# PMIC.net
KiCad netlist of a schematic drawn in Altium Designer
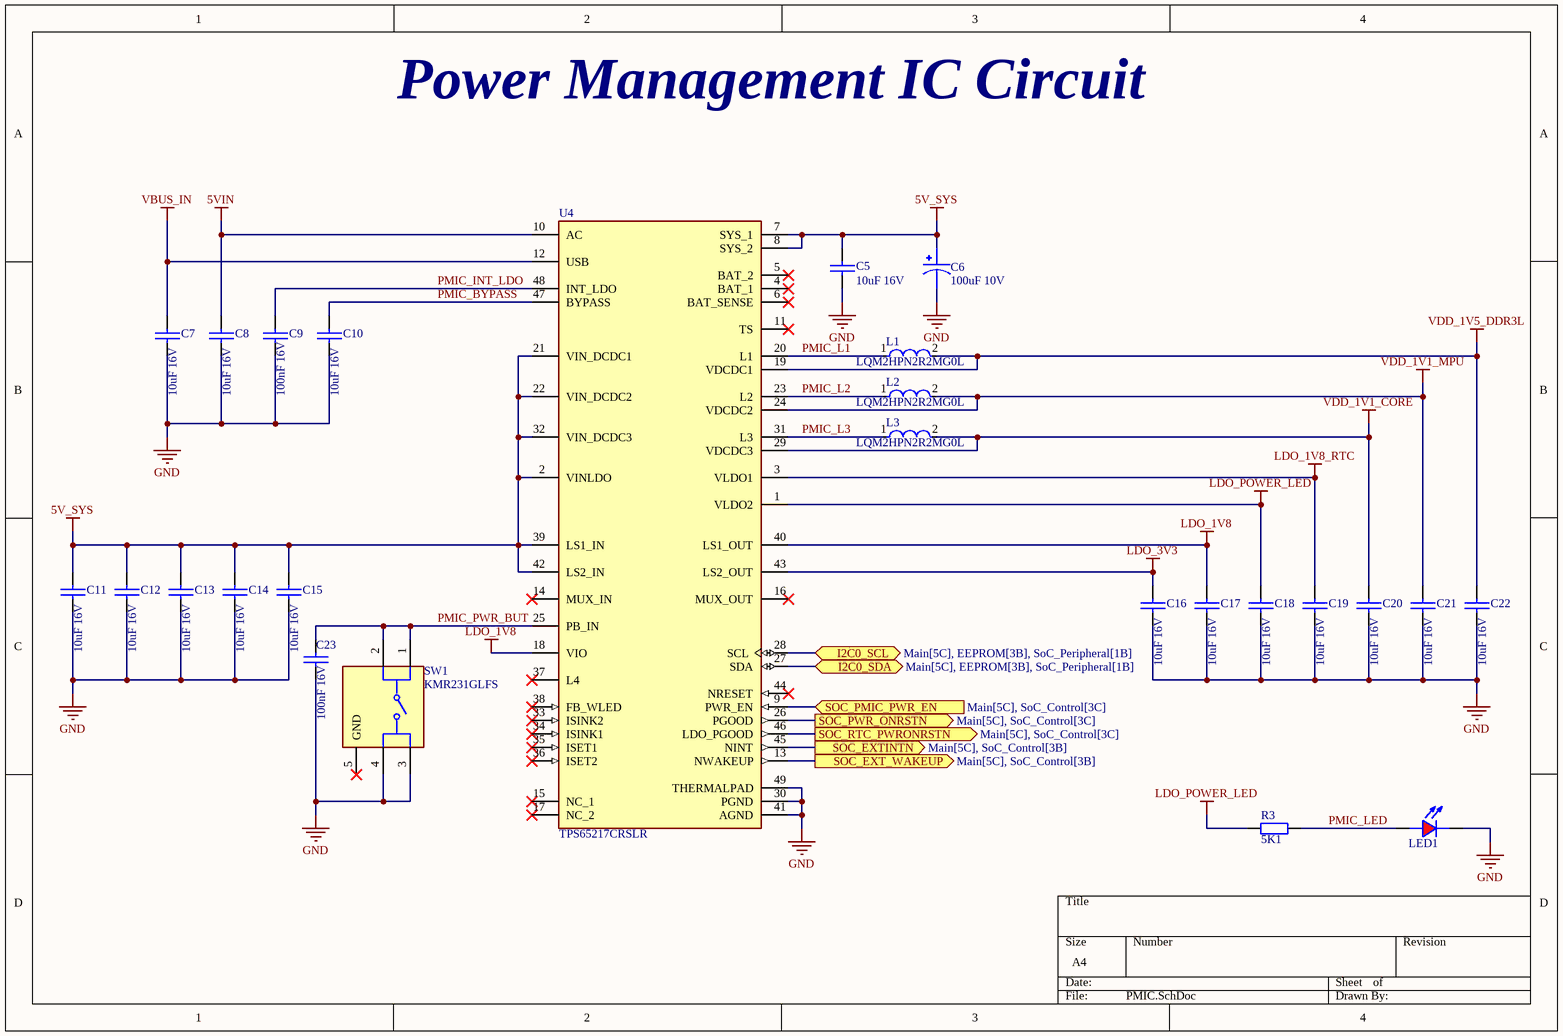
[diagram p0: PMIC.SchDoc]

(export (version "E")
  (design (tool "Eeschema 10.0.6"))
  (components
    (comp (ref "C5")
      (value "10uF 16V")
      (footprint "C_0603")
      (description "Capacitor 0603 SMD")
      (libsource (lib "tor1kkLib") (part "C_0603"))
    )
    (comp (ref "C6")
      (value "100uF 10V")
      (footprint "C_CASE-B")
      (description "Tantalum capacitor CASE-B-3528-21")
      (libsource (lib "tor1kkLib") (part "C_CASE-B-3528-21"))
    )
    (comp (ref "C7")
      (value "10uF 16V")
      (footprint "C_0603")
      (description "Capacitor 0603 SMD")
      (libsource (lib "tor1kkLib") (part "C_0603"))
    )
    (comp (ref "C8")
      (value "10uF 16V")
      (footprint "C_0603")
      (description "Capacitor 0603 SMD")
      (libsource (lib "tor1kkLib") (part "C_0603"))
    )
    (comp (ref "C9")
      (value "100nF 16V")
      (footprint "C_0402")
      (description "Capacitor 0402 SMD")
      (libsource (lib "tor1kkLib") (part "C_0402"))
    )
    (comp (ref "C10")
      (value "10uF 16V")
      (footprint "C_0603")
      (description "Capacitor 0603 SMD")
      (libsource (lib "tor1kkLib") (part "C_0603"))
    )
    (comp (ref "C11")
      (value "10uF 16V")
      (footprint "C_0603")
      (description "Capacitor 0603 SMD")
      (libsource (lib "tor1kkLib") (part "C_0603"))
    )
    (comp (ref "C12")
      (value "10uF 16V")
      (footprint "C_0603")
      (description "Capacitor 0603 SMD")
      (libsource (lib "tor1kkLib") (part "C_0603"))
    )
    (comp (ref "C13")
      (value "10uF 16V")
      (footprint "C_0603")
      (description "Capacitor 0603 SMD")
      (libsource (lib "tor1kkLib") (part "C_0603"))
    )
    (comp (ref "C14")
      (value "10uF 16V")
      (footprint "C_0603")
      (description "Capacitor 0603 SMD")
      (libsource (lib "tor1kkLib") (part "C_0603"))
    )
    (comp (ref "C15")
      (value "10uF 16V")
      (footprint "C_0603")
      (description "Capacitor 0603 SMD")
      (libsource (lib "tor1kkLib") (part "C_0603"))
    )
    (comp (ref "C16")
      (value "10uF 16V")
      (footprint "C_0603")
      (description "Capacitor 0603 SMD")
      (libsource (lib "tor1kkLib") (part "C_0603"))
    )
    (comp (ref "C17")
      (value "10uF 16V")
      (footprint "C_0603")
      (description "Capacitor 0603 SMD")
      (libsource (lib "tor1kkLib") (part "C_0603"))
    )
    (comp (ref "C18")
      (value "10uF 16V")
      (footprint "C_0603")
      (description "Capacitor 0603 SMD")
      (libsource (lib "tor1kkLib") (part "C_0603"))
    )
    (comp (ref "C19")
      (value "10uF 16V")
      (footprint "C_0603")
      (description "Capacitor 0603 SMD")
      (libsource (lib "tor1kkLib") (part "C_0603"))
    )
    (comp (ref "C20")
      (value "10uF 16V")
      (footprint "C_0603")
      (description "Capacitor 0603 SMD")
      (libsource (lib "tor1kkLib") (part "C_0603"))
    )
    (comp (ref "C21")
      (value "10uF 16V")
      (footprint "C_0603")
      (description "Capacitor 0603 SMD")
      (libsource (lib "tor1kkLib") (part "C_0603"))
    )
    (comp (ref "C22")
      (value "10uF 16V")
      (footprint "C_0603")
      (description "Capacitor 0603 SMD")
      (libsource (lib "tor1kkLib") (part "C_0603"))
    )
    (comp (ref "C23")
      (value "100nF 16V")
      (footprint "C_0402")
      (description "Capacitor 0402 SMD")
      (libsource (lib "tor1kkLib") (part "C_0402"))
    )
    (comp (ref "L1")
      (value "LQM2HPN2R2MG0L")
      (footprint "FP-LQM2HPN_G0-IPC_C")
      (description "Multilayer Type Inductor for Power Lines, 1008 (2520), 2.2μH, 20%, 0.1Ω, 1.3A")
      (fields (field (name "TOLERANCE") "20%"))
      (libsource (lib "Altium Content Vault") (part "725321dda6339637d4d059423bc1c3c"))
    )
    (comp (ref "L2")
      (value "LQM2HPN2R2MG0L")
      (footprint "FP-LQM2HPN_G0-IPC_C")
      (description "Multilayer Type Inductor for Power Lines, 1008 (2520), 2.2μH, 20%, 0.1Ω, 1.3A")
      (fields (field (name "TOLERANCE") "20%"))
      (libsource (lib "Altium Content Vault") (part "725321dda6339637d4d059423bc1c3c"))
    )
    (comp (ref "L3")
      (value "LQM2HPN2R2MG0L")
      (footprint "FP-LQM2HPN_G0-IPC_C")
      (description "Multilayer Type Inductor for Power Lines, 1008 (2520), 2.2μH, 20%, 0.1Ω, 1.3A")
      (fields (field (name "TOLERANCE") "20%"))
      (libsource (lib "Altium Content Vault") (part "725321dda6339637d4d059423bc1c3c"))
    )
    (comp (ref "LED1")
      (value "LED_0603_RED")
      (footprint "LED_0603")
      (libsource (lib "tor1kkLib") (part "LED_0603_RED"))
    )
    (comp (ref "R3")
      (value "5K1")
      (footprint "R_0603")
      (description "Resistor 0603 SMD")
      (libsource (lib "tor1kkLib") (part "R_0603"))
    )
    (comp (ref "SW1")
      (value "KMR231GLFS")
      (footprint "FP-KMR231GLFS-MFG")
      (description "SWITCH TACTILE SPST-NO 0.05A 32V")
      (libsource (lib "Altium Content Vault") (part "4ba73034ab40b7b0ce053ff7ec1e5b4"))
    )
    (comp (ref "U4")
      (value "TPS65217CRSLR")
      (footprint "QFN40P600X600X100-49N-D")
      (description "TPS65217 Single-Chip PMIC for Battery-Powered Systems")
      (fields (field (name "MANUFACTURER") "Texas Instruments"))
      (libsource (lib "tor1kkLib") (part "TPS65217CRSLR"))
    )
  )
  (nets
    (net (code "1") (name "/I2C0_SCL") (class "Default")
      (node (ref "U4") (pin "28") (pinfunction "SCL_28") (pintype "bidirectional"))
    )
    (net (code "2") (name "/I2C0_SDA") (class "Default")
      (node (ref "U4") (pin "27") (pinfunction "SDA_27") (pintype "bidirectional"))
    )
    (net (code "3") (name "/PMIC_BYPASS") (class "Default")
      (node (ref "C10") (pin "1") (pintype "passive"))
      (node (ref "U4") (pin "47") (pinfunction "BYPASS_47") (pintype "passive"))
    )
    (net (code "4") (name "/PMIC_INT_LDO") (class "Default")
      (node (ref "C9") (pin "1") (pintype "passive"))
      (node (ref "U4") (pin "48") (pinfunction "INT_LDO_48") (pintype "passive"))
    )
    (net (code "5") (name "/PMIC_L1") (class "Default")
      (node (ref "L1") (pin "1") (pinfunction "1_1") (pintype "passive"))
      (node (ref "U4") (pin "20") (pinfunction "L1_20") (pintype "passive"))
    )
    (net (code "6") (name "/PMIC_L2") (class "Default")
      (node (ref "L2") (pin "1") (pinfunction "1_1") (pintype "passive"))
      (node (ref "U4") (pin "23") (pinfunction "L2_23") (pintype "passive"))
    )
    (net (code "7") (name "/PMIC_L3") (class "Default")
      (node (ref "L3") (pin "1") (pinfunction "1_1") (pintype "passive"))
      (node (ref "U4") (pin "31") (pinfunction "L3_31") (pintype "passive"))
    )
    (net (code "8") (name "/PMIC_LED") (class "Default")
      (node (ref "LED1") (pin "1") (pinfunction "A_1") (pintype "passive"))
      (node (ref "R3") (pin "1") (pintype "passive"))
    )
    (net (code "9") (name "/PMIC_PWR_BUT") (class "Default")
      (node (ref "C23") (pin "1") (pintype "passive"))
      (node (ref "SW1") (pin "1") (pinfunction "1_1") (pintype "passive"))
      (node (ref "SW1") (pin "2") (pinfunction "2_2") (pintype "passive"))
      (node (ref "U4") (pin "25") (pinfunction "PB_IN_25") (pintype "passive"))
    )
    (net (code "10") (name "/SOC_EXTINTN") (class "Default")
      (node (ref "U4") (pin "45") (pinfunction "NINT_45") (pintype "output"))
    )
    (net (code "11") (name "/SOC_EXT_WAKEUP") (class "Default")
      (node (ref "U4") (pin "13") (pinfunction "NWAKEUP_13") (pintype "output"))
    )
    (net (code "12") (name "/SOC_PMIC_PWR_EN") (class "Default")
      (node (ref "U4") (pin "9") (pinfunction "PWR_EN_9") (pintype "input"))
    )
    (net (code "13") (name "/SOC_PWR_ONRSTN") (class "Default")
      (node (ref "U4") (pin "26") (pinfunction "PGOOD_26") (pintype "output"))
    )
    (net (code "14") (name "/SOC_RTC_PWRONRSTN") (class "Default")
      (node (ref "U4") (pin "46") (pinfunction "LDO_PGOOD_46") (pintype "output"))
    )
    (net (code "15") (name "5VIN") (class "Default")
      (node (ref "C8") (pin "1") (pintype "passive"))
      (node (ref "U4") (pin "10") (pinfunction "AC_10") (pintype "passive"))
    )
    (net (code "16") (name "5V_SYS") (class "Default")
      (node (ref "C11") (pin "1") (pintype "passive"))
      (node (ref "C12") (pin "1") (pintype "passive"))
      (node (ref "C13") (pin "1") (pintype "passive"))
      (node (ref "C14") (pin "1") (pintype "passive"))
      (node (ref "C15") (pin "1") (pintype "passive"))
      (node (ref "C5") (pin "1") (pintype "passive"))
      (node (ref "C6") (pin "1") (pinfunction "1_1") (pintype "passive"))
      (node (ref "U4") (pin "2") (pinfunction "VINLDO_2") (pintype "passive"))
      (node (ref "U4") (pin "21") (pinfunction "VIN_DCDC1_21") (pintype "passive"))
      (node (ref "U4") (pin "22") (pinfunction "VIN_DCDC2_22") (pintype "passive"))
      (node (ref "U4") (pin "32") (pinfunction "VIN_DCDC3_32") (pintype "passive"))
      (node (ref "U4") (pin "39") (pinfunction "LS1_IN_39") (pintype "passive"))
      (node (ref "U4") (pin "42") (pinfunction "LS2_IN_42") (pintype "passive"))
      (node (ref "U4") (pin "7") (pinfunction "SYS_1_7") (pintype "passive"))
      (node (ref "U4") (pin "8") (pinfunction "SYS_2_8") (pintype "passive"))
    )
    (net (code "17") (name "GND") (class "Default")
      (node (ref "C10") (pin "2") (pintype "passive"))
      (node (ref "C11") (pin "2") (pintype "passive"))
      (node (ref "C12") (pin "2") (pintype "passive"))
      (node (ref "C13") (pin "2") (pintype "passive"))
      (node (ref "C14") (pin "2") (pintype "passive"))
      (node (ref "C15") (pin "2") (pintype "passive"))
      (node (ref "C16") (pin "2") (pintype "passive"))
      (node (ref "C17") (pin "2") (pintype "passive"))
      (node (ref "C18") (pin "2") (pintype "passive"))
      (node (ref "C19") (pin "2") (pintype "passive"))
      (node (ref "C20") (pin "2") (pintype "passive"))
      (node (ref "C21") (pin "2") (pintype "passive"))
      (node (ref "C22") (pin "2") (pintype "passive"))
      (node (ref "C23") (pin "2") (pintype "passive"))
      (node (ref "C5") (pin "2") (pintype "passive"))
      (node (ref "C6") (pin "2") (pinfunction "2_2") (pintype "passive"))
      (node (ref "C7") (pin "2") (pintype "passive"))
      (node (ref "C8") (pin "2") (pintype "passive"))
      (node (ref "C9") (pin "2") (pintype "passive"))
      (node (ref "LED1") (pin "2") (pinfunction "C_2") (pintype "passive"))
      (node (ref "SW1") (pin "3") (pinfunction "3_3") (pintype "passive"))
      (node (ref "SW1") (pin "4") (pinfunction "4_4") (pintype "passive"))
      (node (ref "U4") (pin "30") (pinfunction "PGND_30") (pintype "passive"))
      (node (ref "U4") (pin "41") (pinfunction "AGND_41") (pintype "passive"))
      (node (ref "U4") (pin "49") (pinfunction "THERMALPAD_49") (pintype "passive"))
    )
    (net (code "18") (name "LDO_1V8") (class "Default")
      (node (ref "C17") (pin "1") (pintype "passive"))
      (node (ref "U4") (pin "18") (pinfunction "VIO_18") (pintype "passive"))
      (node (ref "U4") (pin "40") (pinfunction "LS1_OUT_40") (pintype "passive"))
    )
    (net (code "19") (name "LDO_1V8_RTC") (class "Default")
      (node (ref "C19") (pin "1") (pintype "passive"))
      (node (ref "U4") (pin "3") (pinfunction "VLDO1_3") (pintype "passive"))
    )
    (net (code "20") (name "LDO_3V3") (class "Default")
      (node (ref "C16") (pin "1") (pintype "passive"))
      (node (ref "U4") (pin "43") (pinfunction "LS2_OUT_43") (pintype "passive"))
    )
    (net (code "21") (name "LDO_POWER_LED") (class "Default")
      (node (ref "C18") (pin "1") (pintype "passive"))
      (node (ref "R3") (pin "2") (pintype "passive"))
      (node (ref "U4") (pin "1") (pinfunction "VLDO2_1") (pintype "passive"))
    )
    (net (code "22") (name "VBUS_IN") (class "Default")
      (node (ref "C7") (pin "1") (pintype "passive"))
      (node (ref "U4") (pin "12") (pinfunction "USB_12") (pintype "passive"))
    )
    (net (code "23") (name "VDD_1V1_CORE") (class "Default")
      (node (ref "C20") (pin "1") (pintype "passive"))
      (node (ref "L3") (pin "2") (pinfunction "2_2") (pintype "passive"))
      (node (ref "U4") (pin "29") (pinfunction "VDCDC3_29") (pintype "passive"))
    )
    (net (code "24") (name "VDD_1V1_MPU") (class "Default")
      (node (ref "C21") (pin "1") (pintype "passive"))
      (node (ref "L2") (pin "2") (pinfunction "2_2") (pintype "passive"))
      (node (ref "U4") (pin "24") (pinfunction "VDCDC2_24") (pintype "passive"))
    )
    (net (code "25") (name "VDD_1V5_DDR3L") (class "Default")
      (node (ref "C22") (pin "1") (pintype "passive"))
      (node (ref "L1") (pin "2") (pinfunction "2_2") (pintype "passive"))
      (node (ref "U4") (pin "19") (pinfunction "VDCDC1_19") (pintype "passive"))
    )
    (net (code "26") (name "unconnected-(SW1-GND-Pad5)") (class "Default")
      (node (ref "SW1") (pin "5") (pinfunction "GND_5") (pintype "power_in+no_connect"))
    )
    (net (code "27") (name "unconnected-(U4-BAT_1-Pad4)") (class "Default")
      (node (ref "U4") (pin "4") (pinfunction "BAT_1_4") (pintype "passive+no_connect"))
    )
    (net (code "28") (name "unconnected-(U4-BAT_2-Pad5)") (class "Default")
      (node (ref "U4") (pin "5") (pinfunction "BAT_2_5") (pintype "passive+no_connect"))
    )
    (net (code "29") (name "unconnected-(U4-BAT_SENSE-Pad6)") (class "Default")
      (node (ref "U4") (pin "6") (pinfunction "BAT_SENSE_6") (pintype "passive+no_connect"))
    )
    (net (code "30") (name "unconnected-(U4-FB_WLED-Pad38)") (class "Default")
      (node (ref "U4") (pin "38") (pinfunction "FB_WLED_38") (pintype "input+no_connect"))
    )
    (net (code "31") (name "unconnected-(U4-ISET1-Pad35)") (class "Default")
      (node (ref "U4") (pin "35") (pinfunction "ISET1_35") (pintype "input+no_connect"))
    )
    (net (code "32") (name "unconnected-(U4-ISET2-Pad36)") (class "Default")
      (node (ref "U4") (pin "36") (pinfunction "ISET2_36") (pintype "input+no_connect"))
    )
    (net (code "33") (name "unconnected-(U4-ISINK1-Pad34)") (class "Default")
      (node (ref "U4") (pin "34") (pinfunction "ISINK1_34") (pintype "input+no_connect"))
    )
    (net (code "34") (name "unconnected-(U4-ISINK2-Pad33)") (class "Default")
      (node (ref "U4") (pin "33") (pinfunction "ISINK2_33") (pintype "input+no_connect"))
    )
    (net (code "35") (name "unconnected-(U4-L4-Pad37)") (class "Default")
      (node (ref "U4") (pin "37") (pinfunction "L4_37") (pintype "passive+no_connect"))
    )
    (net (code "36") (name "unconnected-(U4-MUX_IN-Pad14)") (class "Default")
      (node (ref "U4") (pin "14") (pinfunction "MUX_IN_14") (pintype "passive+no_connect"))
    )
    (net (code "37") (name "unconnected-(U4-MUX_OUT-Pad16)") (class "Default")
      (node (ref "U4") (pin "16") (pinfunction "MUX_OUT_16") (pintype "passive+no_connect"))
    )
    (net (code "38") (name "unconnected-(U4-NC_1-Pad15)") (class "Default")
      (node (ref "U4") (pin "15") (pinfunction "NC_1_15") (pintype "passive+no_connect"))
    )
    (net (code "39") (name "unconnected-(U4-NC_2-Pad17)") (class "Default")
      (node (ref "U4") (pin "17") (pinfunction "NC_2_17") (pintype "passive+no_connect"))
    )
    (net (code "40") (name "unconnected-(U4-NRESET-Pad44)") (class "Default")
      (node (ref "U4") (pin "44") (pinfunction "NRESET_44") (pintype "input+no_connect"))
    )
    (net (code "41") (name "unconnected-(U4-TS-Pad11)") (class "Default")
      (node (ref "U4") (pin "11") (pinfunction "TS_11") (pintype "passive+no_connect"))
    )
  )
)
